# LB_BIT_i33_envelope-v03_3_3.net
KiCad netlist of a schematic drawn in EAGLE
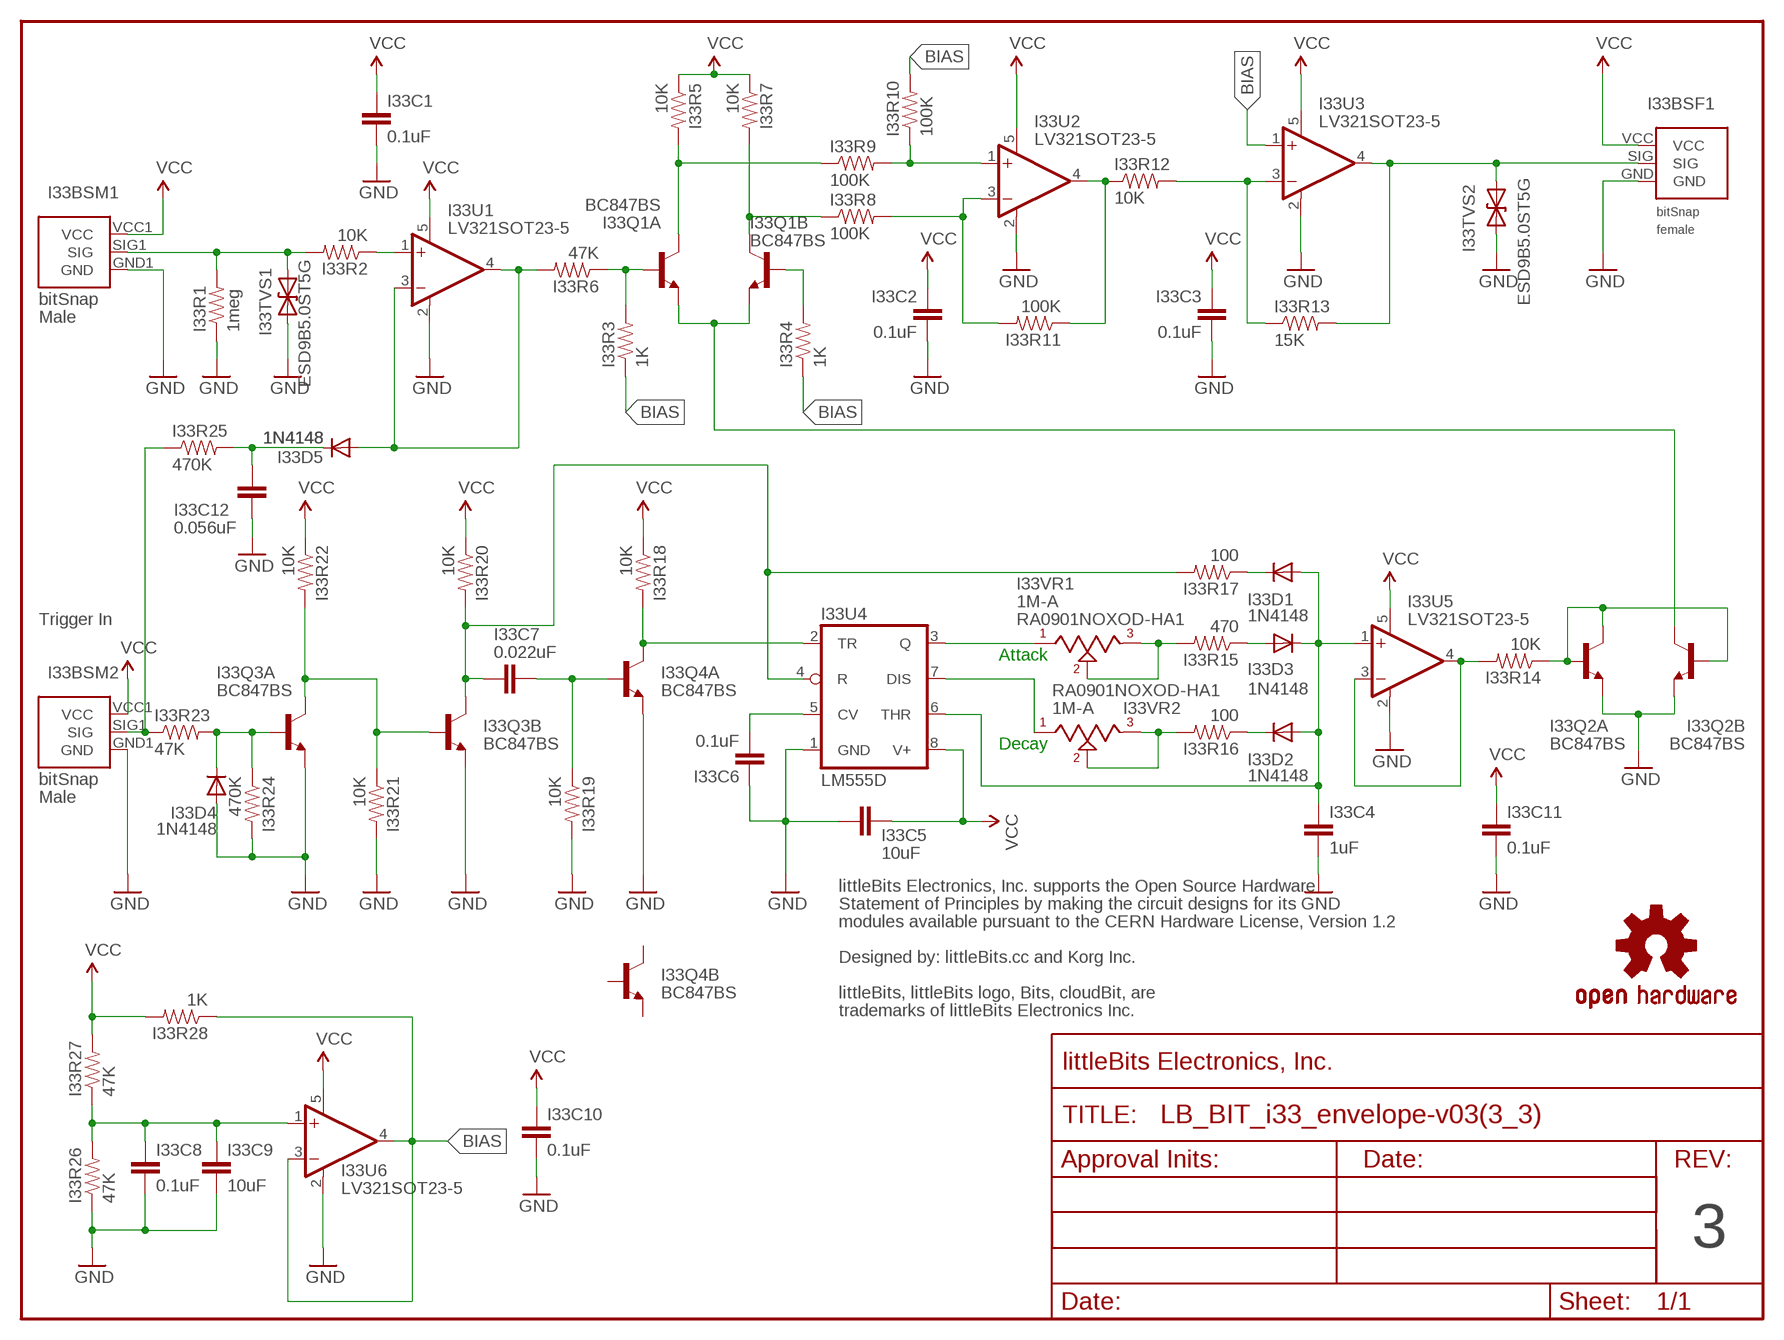
[diagram p0: schematic, sheet 1]

(export (version "E")
  (design (tool "Eeschema 10.0.6"))
  (components
    (comp (ref "I33BSF1")
      (value "BITSNAP_V03_FEMALE")
      (footprint "eagle-import:BITSNAP_V03_FEMALE")
      (libsource (lib "eagle-import") (part "BITSNAP_V03_FEMALE"))
    )
    (comp (ref "I33BSM1")
      (value "BITSNAP_V03_MALE")
      (footprint "eagle-import:BITSNAP_V03_MALE")
      (libsource (lib "eagle-import") (part "BITSNAP_V03_MALE"))
    )
    (comp (ref "I33BSM2")
      (value "BITSNAP_V03_MALE")
      (footprint "eagle-import:BITSNAP_V03_MALE")
      (libsource (lib "eagle-import") (part "BITSNAP_V03_MALE"))
    )
    (comp (ref "I33C1")
      (value "0.1uF")
      (footprint "eagle-import:CAP-0603")
      (libsource (lib "eagle-import") (part "CAPCAP-0603"))
    )
    (comp (ref "I33C2")
      (value "0.1uF")
      (footprint "eagle-import:CAP-0603")
      (libsource (lib "eagle-import") (part "CAPCAP-0603"))
    )
    (comp (ref "I33C3")
      (value "0.1uF")
      (footprint "eagle-import:CAP-0603")
      (libsource (lib "eagle-import") (part "CAPCAP-0603"))
    )
    (comp (ref "I33C4")
      (value "1uF")
      (footprint "eagle-import:CAP-0603")
      (libsource (lib "eagle-import") (part "CAPCAP-0603"))
    )
    (comp (ref "I33C5")
      (value "10uF")
      (footprint "eagle-import:CAP-0603")
      (libsource (lib "eagle-import") (part "CAPCAP-0603"))
    )
    (comp (ref "I33C6")
      (value "0.1uF")
      (footprint "eagle-import:CAP-0603")
      (libsource (lib "eagle-import") (part "CAPCAP-0603"))
    )
    (comp (ref "I33C7")
      (value "0.022uF")
      (footprint "eagle-import:CAP-0603")
      (libsource (lib "eagle-import") (part "CAPCAP-0603"))
    )
    (comp (ref "I33C8")
      (value "0.1uF")
      (footprint "eagle-import:CAP-0603")
      (libsource (lib "eagle-import") (part "CAPCAP-0603"))
    )
    (comp (ref "I33C9")
      (value "10uF")
      (footprint "eagle-import:CAP-0603")
      (libsource (lib "eagle-import") (part "CAPCAP-0603"))
    )
    (comp (ref "I33C10")
      (value "0.1uF")
      (footprint "eagle-import:CAP-0603")
      (libsource (lib "eagle-import") (part "CAPCAP-0603"))
    )
    (comp (ref "I33C11")
      (value "0.1uF")
      (footprint "eagle-import:CAP-0603")
      (libsource (lib "eagle-import") (part "CAPCAP-0603"))
    )
    (comp (ref "I33C12")
      (value "0.056uF")
      (footprint "eagle-import:CAP-0603")
      (libsource (lib "eagle-import") (part "CAPCAP-0603"))
    )
    (comp (ref "I33D1")
      (value "1N4148")
      (footprint "eagle-import:SOD-323")
      (libsource (lib "eagle-import") (part "DIODESOD"))
    )
    (comp (ref "I33D2")
      (value "1N4148")
      (footprint "eagle-import:SOD-323")
      (libsource (lib "eagle-import") (part "DIODESOD"))
    )
    (comp (ref "I33D3")
      (value "1N4148")
      (footprint "eagle-import:SOD-323")
      (libsource (lib "eagle-import") (part "DIODESOD"))
    )
    (comp (ref "I33D4")
      (value "1N4148")
      (footprint "eagle-import:SOD-323")
      (libsource (lib "eagle-import") (part "DIODESOD"))
    )
    (comp (ref "I33D5")
      (value "1N4148")
      (footprint "eagle-import:SOD-323")
      (libsource (lib "eagle-import") (part "DIODESOD"))
    )
    (comp (ref "I33Q1")
      (value "BC847BS")
      (footprint "eagle-import:SOT-363_PHILLIPS")
      (libsource (lib "eagle-import") (part "TRANS-BJT_NPN-DUAL-BC847BS"))
    )
    (comp (ref "I33Q2")
      (value "BC847BS")
      (footprint "eagle-import:SOT-363_PHILLIPS")
      (libsource (lib "eagle-import") (part "TRANS-BJT_NPN-DUAL-BC847BS"))
    )
    (comp (ref "I33Q3")
      (value "BC847BS")
      (footprint "eagle-import:SOT-363_PHILLIPS")
      (libsource (lib "eagle-import") (part "TRANS-BJT_NPN-DUAL-BC847BS"))
    )
    (comp (ref "I33Q4")
      (value "BC847BS")
      (footprint "eagle-import:SOT-363_PHILLIPS")
      (libsource (lib "eagle-import") (part "TRANS-BJT_NPN-DUAL-BC847BS"))
    )
    (comp (ref "I33R1")
      (value "1meg")
      (footprint "eagle-import:RES-0603")
      (libsource (lib "eagle-import") (part "RESISTOR0603"))
    )
    (comp (ref "I33R2")
      (value "10K")
      (footprint "eagle-import:RES-0603")
      (libsource (lib "eagle-import") (part "RESISTOR0603"))
    )
    (comp (ref "I33R3")
      (value "1K")
      (footprint "eagle-import:RES-0603")
      (libsource (lib "eagle-import") (part "RESISTOR0603"))
    )
    (comp (ref "I33R4")
      (value "1K")
      (footprint "eagle-import:RES-0603")
      (libsource (lib "eagle-import") (part "RESISTOR0603"))
    )
    (comp (ref "I33R5")
      (value "10K")
      (footprint "eagle-import:RES-0603")
      (libsource (lib "eagle-import") (part "RESISTOR0603"))
    )
    (comp (ref "I33R6")
      (value "47K")
      (footprint "eagle-import:RES-0603")
      (libsource (lib "eagle-import") (part "RESISTOR0603"))
    )
    (comp (ref "I33R7")
      (value "10K")
      (footprint "eagle-import:RES-0603")
      (libsource (lib "eagle-import") (part "RESISTOR0603"))
    )
    (comp (ref "I33R8")
      (value "100K")
      (footprint "eagle-import:RES-0603")
      (libsource (lib "eagle-import") (part "RESISTOR0603"))
    )
    (comp (ref "I33R9")
      (value "100K")
      (footprint "eagle-import:RES-0603")
      (libsource (lib "eagle-import") (part "RESISTOR0603"))
    )
    (comp (ref "I33R10")
      (value "100K")
      (footprint "eagle-import:RES-0603")
      (libsource (lib "eagle-import") (part "RESISTOR0603"))
    )
    (comp (ref "I33R11")
      (value "100K")
      (footprint "eagle-import:RES-0603")
      (libsource (lib "eagle-import") (part "RESISTOR0603"))
    )
    (comp (ref "I33R12")
      (value "10K")
      (footprint "eagle-import:RES-0603")
      (libsource (lib "eagle-import") (part "RESISTOR0603"))
    )
    (comp (ref "I33R13")
      (value "15K")
      (footprint "eagle-import:RES-0603")
      (libsource (lib "eagle-import") (part "RESISTOR0603"))
    )
    (comp (ref "I33R14")
      (value "10K")
      (footprint "eagle-import:RES-0603")
      (libsource (lib "eagle-import") (part "RESISTOR0603"))
    )
    (comp (ref "I33R15")
      (value "470")
      (footprint "eagle-import:RES-0603")
      (libsource (lib "eagle-import") (part "RESISTOR0603"))
    )
    (comp (ref "I33R16")
      (value "100")
      (footprint "eagle-import:RES-0603")
      (libsource (lib "eagle-import") (part "RESISTOR0603"))
    )
    (comp (ref "I33R17")
      (value "100")
      (footprint "eagle-import:RES-0603")
      (libsource (lib "eagle-import") (part "RESISTOR0603"))
    )
    (comp (ref "I33R18")
      (value "10K")
      (footprint "eagle-import:RES-0603")
      (libsource (lib "eagle-import") (part "RESISTOR0603"))
    )
    (comp (ref "I33R19")
      (value "10K")
      (footprint "eagle-import:RES-0603")
      (libsource (lib "eagle-import") (part "RESISTOR0603"))
    )
    (comp (ref "I33R20")
      (value "10K")
      (footprint "eagle-import:RES-0603")
      (libsource (lib "eagle-import") (part "RESISTOR0603"))
    )
    (comp (ref "I33R21")
      (value "10K")
      (footprint "eagle-import:RES-0603")
      (libsource (lib "eagle-import") (part "RESISTOR0603"))
    )
    (comp (ref "I33R22")
      (value "10K")
      (footprint "eagle-import:RES-0603")
      (libsource (lib "eagle-import") (part "RESISTOR0603"))
    )
    (comp (ref "I33R23")
      (value "47K")
      (footprint "eagle-import:RES-0603")
      (libsource (lib "eagle-import") (part "RESISTOR0603"))
    )
    (comp (ref "I33R24")
      (value "470K")
      (footprint "eagle-import:RES-0603")
      (libsource (lib "eagle-import") (part "RESISTOR0603"))
    )
    (comp (ref "I33R25")
      (value "470K")
      (footprint "eagle-import:RES-0603")
      (libsource (lib "eagle-import") (part "RESISTOR0603"))
    )
    (comp (ref "I33R26")
      (value "47K")
      (footprint "eagle-import:RES-0603")
      (libsource (lib "eagle-import") (part "RESISTOR0603"))
    )
    (comp (ref "I33R27")
      (value "47K")
      (footprint "eagle-import:RES-0603")
      (libsource (lib "eagle-import") (part "RESISTOR0603"))
    )
    (comp (ref "I33R28")
      (value "1K")
      (footprint "eagle-import:RES-0603")
      (libsource (lib "eagle-import") (part "RESISTOR0603"))
    )
    (comp (ref "I33TVS1")
      (value "ESD9B5.0ST5G")
      (footprint "eagle-import:SOD-923")
      (libsource (lib "eagle-import") (part "DIODE-TVSSOD-923"))
    )
    (comp (ref "I33TVS2")
      (value "ESD9B5.0ST5G")
      (footprint "eagle-import:SOD-923")
      (libsource (lib "eagle-import") (part "DIODE-TVSSOD-923"))
    )
    (comp (ref "I33U1")
      (value "LV321SOT23-5")
      (footprint "eagle-import:SOT23-5")
      (libsource (lib "eagle-import") (part "LV321SOT23-5"))
    )
    (comp (ref "I33U2")
      (value "LV321SOT23-5")
      (footprint "eagle-import:SOT23-5")
      (libsource (lib "eagle-import") (part "LV321SOT23-5"))
    )
    (comp (ref "I33U3")
      (value "LV321SOT23-5")
      (footprint "eagle-import:SOT23-5")
      (libsource (lib "eagle-import") (part "LV321SOT23-5"))
    )
    (comp (ref "I33U4")
      (value "LM555D")
      (footprint "eagle-import:SO08")
      (libsource (lib "eagle-import") (part "LM555D"))
    )
    (comp (ref "I33U5")
      (value "LV321SOT23-5")
      (footprint "eagle-import:SOT23-5")
      (libsource (lib "eagle-import") (part "LV321SOT23-5"))
    )
    (comp (ref "I33U6")
      (value "LV321SOT23-5")
      (footprint "eagle-import:SOT23-5")
      (libsource (lib "eagle-import") (part "LV321SOT23-5"))
    )
    (comp (ref "I33VR1")
      (value "1M-A")
      (footprint "eagle-import:ALPS_POT")
      (libsource (lib "eagle-import") (part "ALPS_POTTH"))
    )
    (comp (ref "I33VR2")
      (value "1M-A")
      (footprint "eagle-import:ALPS_POT")
      (libsource (lib "eagle-import") (part "ALPS_POTTH"))
    )
    (comp (ref "U$1")
      (value "FRAME-LETTER-OHWOHW")
      (footprint "eagle-import:FABDWG01-OHW")
      (libsource (lib "eagle-import") (part "FRAME-LETTER-OHWOHW"))
    )
    (comp (ref "U$3")
      (value "OSHWCREDIT-KORG")
      (footprint "eagle-import:OSHWCREDIT-KORG")
      (libsource (lib "eagle-import") (part "OSHWCREDIT-KORG"))
    )
    (comp (ref "U$9")
      (value "OSHW-LOGOL")
      (footprint "eagle-import:OSHW-LOGO-L")
      (libsource (lib "eagle-import") (part "OSHW-LOGOL"))
    )
  )
  (nets
    (net (code "1") (name "BIAS") (class "Default")
      (node (ref "I33R10") (pin "2") (pinfunction "2_2") (pintype "passive"))
      (node (ref "I33R28") (pin "1") (pinfunction "1_1") (pintype "passive"))
      (node (ref "I33R3") (pin "1") (pinfunction "1_1") (pintype "passive"))
      (node (ref "I33R4") (pin "1") (pinfunction "1_1") (pintype "passive"))
      (node (ref "I33U3") (pin "1") (pinfunction "+IN_1") (pintype "input"))
      (node (ref "I33U6") (pin "3") (pinfunction "-IN_3") (pintype "input"))
      (node (ref "I33U6") (pin "4") (pinfunction "OUT_4") (pintype "output"))
    )
    (net (code "2") (name "GND") (class "Default")
      (node (ref "I33BSF1") (pin "GND") (pinfunction "GND_GND") (pintype "bidirectional"))
      (node (ref "I33BSM1") (pin "GND1") (pinfunction "GND_GND1") (pintype "bidirectional"))
      (node (ref "I33BSM2") (pin "GND1") (pinfunction "GND_GND1") (pintype "bidirectional"))
      (node (ref "I33C1") (pin "2") (pinfunction "2_2") (pintype "passive"))
      (node (ref "I33C10") (pin "2") (pinfunction "2_2") (pintype "passive"))
      (node (ref "I33C11") (pin "2") (pinfunction "2_2") (pintype "passive"))
      (node (ref "I33C12") (pin "2") (pinfunction "2_2") (pintype "passive"))
      (node (ref "I33C2") (pin "2") (pinfunction "2_2") (pintype "passive"))
      (node (ref "I33C3") (pin "2") (pinfunction "2_2") (pintype "passive"))
      (node (ref "I33C4") (pin "2") (pinfunction "2_2") (pintype "passive"))
      (node (ref "I33C5") (pin "1") (pinfunction "1_1") (pintype "passive"))
      (node (ref "I33C6") (pin "1") (pinfunction "1_1") (pintype "passive"))
      (node (ref "I33C8") (pin "2") (pinfunction "2_2") (pintype "passive"))
      (node (ref "I33C9") (pin "2") (pinfunction "2_2") (pintype "passive"))
      (node (ref "I33D4") (pin "2") (pinfunction "A_2") (pintype "passive"))
      (node (ref "I33Q2") (pin "1") (pinfunction "E_1") (pintype "passive"))
      (node (ref "I33Q2") (pin "4") (pinfunction "E_4") (pintype "passive"))
      (node (ref "I33Q3") (pin "1") (pinfunction "E_1") (pintype "passive"))
      (node (ref "I33Q3") (pin "4") (pinfunction "E_4") (pintype "passive"))
      (node (ref "I33Q4") (pin "1") (pinfunction "E_1") (pintype "passive"))
      (node (ref "I33R1") (pin "1") (pinfunction "1_1") (pintype "passive"))
      (node (ref "I33R19") (pin "2") (pinfunction "2_2") (pintype "passive"))
      (node (ref "I33R21") (pin "2") (pinfunction "2_2") (pintype "passive"))
      (node (ref "I33R24") (pin "2") (pinfunction "2_2") (pintype "passive"))
      (node (ref "I33R26") (pin "1") (pinfunction "1_1") (pintype "passive"))
      (node (ref "I33TVS1") (pin "1") (pinfunction "A_1") (pintype "passive"))
      (node (ref "I33TVS2") (pin "1") (pinfunction "A_1") (pintype "passive"))
      (node (ref "I33U1") (pin "2") (pinfunction "V-_2") (pintype "power_in"))
      (node (ref "I33U2") (pin "2") (pinfunction "V-_2") (pintype "power_in"))
      (node (ref "I33U3") (pin "2") (pinfunction "V-_2") (pintype "power_in"))
      (node (ref "I33U4") (pin "1") (pinfunction "GND_1") (pintype "power_in"))
      (node (ref "I33U5") (pin "2") (pinfunction "V-_2") (pintype "power_in"))
      (node (ref "I33U6") (pin "2") (pinfunction "V-_2") (pintype "power_in"))
    )
    (net (code "3") (name "Net-(I33BSM1-SIG)") (class "Default")
      (node (ref "I33BSM1") (pin "SIG1") (pinfunction "SIG_SIG1") (pintype "bidirectional"))
      (node (ref "I33R1") (pin "2") (pinfunction "2_2") (pintype "passive"))
      (node (ref "I33R2") (pin "2") (pinfunction "2_2") (pintype "passive"))
      (node (ref "I33TVS1") (pin "2") (pinfunction "C_2") (pintype "passive"))
    )
    (net (code "4") (name "Net-(I33BSM2-SIG)") (class "Default")
      (node (ref "I33BSM2") (pin "SIG1") (pinfunction "SIG_SIG1") (pintype "bidirectional"))
      (node (ref "I33R23") (pin "1") (pinfunction "1_1") (pintype "passive"))
      (node (ref "I33R25") (pin "1") (pinfunction "1_1") (pintype "passive"))
    )
    (net (code "5") (name "Net-(I33D1-A)") (class "Default")
      (node (ref "I33C4") (pin "1") (pinfunction "1_1") (pintype "passive"))
      (node (ref "I33D1") (pin "2") (pinfunction "A_2") (pintype "passive"))
      (node (ref "I33D2") (pin "2") (pinfunction "A_2") (pintype "passive"))
      (node (ref "I33D3") (pin "1") (pinfunction "C_1") (pintype "passive"))
      (node (ref "I33U4") (pin "6") (pinfunction "THR_6") (pintype "input"))
      (node (ref "I33U5") (pin "1") (pinfunction "+IN_1") (pintype "input"))
    )
    (net (code "6") (name "Net-(I33D1-C)") (class "Default")
      (node (ref "I33D1") (pin "1") (pinfunction "C_1") (pintype "passive"))
      (node (ref "I33R17") (pin "1") (pinfunction "1_1") (pintype "passive"))
    )
    (net (code "7") (name "Net-(I33D2-C)") (class "Default")
      (node (ref "I33D2") (pin "1") (pinfunction "C_1") (pintype "passive"))
      (node (ref "I33R16") (pin "1") (pinfunction "1_1") (pintype "passive"))
    )
    (net (code "8") (name "Net-(I33D3-A)") (class "Default")
      (node (ref "I33D3") (pin "2") (pinfunction "A_2") (pintype "passive"))
      (node (ref "I33R15") (pin "1") (pinfunction "1_1") (pintype "passive"))
    )
    (net (code "9") (name "Net-(I33D4-C)") (class "Default")
      (node (ref "I33D4") (pin "1") (pinfunction "C_1") (pintype "passive"))
      (node (ref "I33Q3") (pin "2") (pinfunction "B_2") (pintype "passive"))
      (node (ref "I33R23") (pin "2") (pinfunction "2_2") (pintype "passive"))
      (node (ref "I33R24") (pin "1") (pinfunction "1_1") (pintype "passive"))
    )
    (net (code "10") (name "Net-(I33D5-A)") (class "Default")
      (node (ref "I33D5") (pin "2") (pinfunction "A_2") (pintype "passive"))
      (node (ref "I33R6") (pin "2") (pinfunction "2_2") (pintype "passive"))
      (node (ref "I33U1") (pin "3") (pinfunction "-IN_3") (pintype "input"))
      (node (ref "I33U1") (pin "4") (pinfunction "OUT_4") (pintype "output"))
    )
    (net (code "11") (name "Net-(I33D5-C)") (class "Default")
      (node (ref "I33C12") (pin "1") (pinfunction "1_1") (pintype "passive"))
      (node (ref "I33D5") (pin "1") (pinfunction "C_1") (pintype "passive"))
      (node (ref "I33R25") (pin "2") (pinfunction "2_2") (pintype "passive"))
    )
    (net (code "12") (name "Net-(I33Q1A-B)") (class "Default")
      (node (ref "I33Q1") (pin "2") (pinfunction "B_2") (pintype "passive"))
      (node (ref "I33R3") (pin "2") (pinfunction "2_2") (pintype "passive"))
      (node (ref "I33R6") (pin "1") (pinfunction "1_1") (pintype "passive"))
    )
    (net (code "13") (name "Net-(I33Q1A-C)") (class "Default")
      (node (ref "I33Q1") (pin "6") (pinfunction "C_6") (pintype "passive"))
      (node (ref "I33R5") (pin "2") (pinfunction "2_2") (pintype "passive"))
      (node (ref "I33R9") (pin "1") (pinfunction "1_1") (pintype "passive"))
    )
    (net (code "14") (name "Net-(I33Q1A-E)") (class "Default")
      (node (ref "I33Q1") (pin "1") (pinfunction "E_1") (pintype "passive"))
      (node (ref "I33Q1") (pin "4") (pinfunction "E_4") (pintype "passive"))
      (node (ref "I33Q2") (pin "3") (pinfunction "C_3") (pintype "passive"))
    )
    (net (code "15") (name "Net-(I33Q1B-B)") (class "Default")
      (node (ref "I33Q1") (pin "5") (pinfunction "B_5") (pintype "passive"))
      (node (ref "I33R4") (pin "2") (pinfunction "2_2") (pintype "passive"))
    )
    (net (code "16") (name "Net-(I33Q1B-C)") (class "Default")
      (node (ref "I33Q1") (pin "3") (pinfunction "C_3") (pintype "passive"))
      (node (ref "I33R7") (pin "2") (pinfunction "2_2") (pintype "passive"))
      (node (ref "I33R8") (pin "1") (pinfunction "1_1") (pintype "passive"))
    )
    (net (code "17") (name "Net-(I33Q2A-B)") (class "Default")
      (node (ref "I33Q2") (pin "2") (pinfunction "B_2") (pintype "passive"))
      (node (ref "I33Q2") (pin "5") (pinfunction "B_5") (pintype "passive"))
      (node (ref "I33Q2") (pin "6") (pinfunction "C_6") (pintype "passive"))
      (node (ref "I33R14") (pin "1") (pinfunction "1_1") (pintype "passive"))
    )
    (net (code "18") (name "Net-(I33Q3A-C)") (class "Default")
      (node (ref "I33Q3") (pin "5") (pinfunction "B_5") (pintype "passive"))
      (node (ref "I33Q3") (pin "6") (pinfunction "C_6") (pintype "passive"))
      (node (ref "I33R21") (pin "1") (pinfunction "1_1") (pintype "passive"))
      (node (ref "I33R22") (pin "2") (pinfunction "2_2") (pintype "passive"))
    )
    (net (code "19") (name "Net-(I33Q3B-C)") (class "Default")
      (node (ref "I33C7") (pin "2") (pinfunction "2_2") (pintype "passive"))
      (node (ref "I33Q3") (pin "3") (pinfunction "C_3") (pintype "passive"))
      (node (ref "I33R17") (pin "2") (pinfunction "2_2") (pintype "passive"))
      (node (ref "I33R20") (pin "2") (pinfunction "2_2") (pintype "passive"))
      (node (ref "I33U4") (pin "4") (pinfunction "R_4") (pintype "input"))
    )
    (net (code "20") (name "Net-(I33Q4A-B)") (class "Default")
      (node (ref "I33C7") (pin "1") (pinfunction "1_1") (pintype "passive"))
      (node (ref "I33Q4") (pin "2") (pinfunction "B_2") (pintype "passive"))
      (node (ref "I33R19") (pin "1") (pinfunction "1_1") (pintype "passive"))
    )
    (net (code "21") (name "Net-(I33Q4A-C)") (class "Default")
      (node (ref "I33Q4") (pin "6") (pinfunction "C_6") (pintype "passive"))
      (node (ref "I33R18") (pin "2") (pinfunction "2_2") (pintype "passive"))
      (node (ref "I33U4") (pin "2") (pinfunction "TR_2") (pintype "input"))
    )
    (net (code "22") (name "Net-(I33R15-Pad2)") (class "Default")
      (node (ref "I33R15") (pin "2") (pinfunction "2_2") (pintype "passive"))
      (node (ref "I33VR1") (pin "2") (pinfunction "2_2") (pintype "passive"))
      (node (ref "I33VR1") (pin "3") (pinfunction "3_3") (pintype "passive"))
    )
    (net (code "23") (name "Net-(I33R16-Pad2)") (class "Default")
      (node (ref "I33R16") (pin "2") (pinfunction "2_2") (pintype "passive"))
      (node (ref "I33VR2") (pin "2") (pinfunction "2_2") (pintype "passive"))
      (node (ref "I33VR2") (pin "3") (pinfunction "3_3") (pintype "passive"))
    )
    (net (code "24") (name "Net-(I33TVS2-C)") (class "Default")
      (node (ref "I33BSF1") (pin "SIG") (pinfunction "SIG_SIG") (pintype "bidirectional"))
      (node (ref "I33R13") (pin "2") (pinfunction "2_2") (pintype "passive"))
      (node (ref "I33TVS2") (pin "2") (pinfunction "C_2") (pintype "passive"))
      (node (ref "I33U3") (pin "4") (pinfunction "OUT_4") (pintype "output"))
    )
    (net (code "25") (name "Net-(I33U1-+IN)") (class "Default")
      (node (ref "I33R2") (pin "1") (pinfunction "1_1") (pintype "passive"))
      (node (ref "I33U1") (pin "1") (pinfunction "+IN_1") (pintype "input"))
    )
    (net (code "26") (name "Net-(I33U2-+IN)") (class "Default")
      (node (ref "I33R10") (pin "1") (pinfunction "1_1") (pintype "passive"))
      (node (ref "I33R9") (pin "2") (pinfunction "2_2") (pintype "passive"))
      (node (ref "I33U2") (pin "1") (pinfunction "+IN_1") (pintype "input"))
    )
    (net (code "27") (name "Net-(I33U2--IN)") (class "Default")
      (node (ref "I33R11") (pin "2") (pinfunction "2_2") (pintype "passive"))
      (node (ref "I33R8") (pin "2") (pinfunction "2_2") (pintype "passive"))
      (node (ref "I33U2") (pin "3") (pinfunction "-IN_3") (pintype "input"))
    )
    (net (code "28") (name "Net-(I33U2-OUT)") (class "Default")
      (node (ref "I33R11") (pin "1") (pinfunction "1_1") (pintype "passive"))
      (node (ref "I33R12") (pin "1") (pinfunction "1_1") (pintype "passive"))
      (node (ref "I33U2") (pin "4") (pinfunction "OUT_4") (pintype "output"))
    )
    (net (code "29") (name "Net-(I33U3--IN)") (class "Default")
      (node (ref "I33R12") (pin "2") (pinfunction "2_2") (pintype "passive"))
      (node (ref "I33R13") (pin "1") (pinfunction "1_1") (pintype "passive"))
      (node (ref "I33U3") (pin "3") (pinfunction "-IN_3") (pintype "input"))
    )
    (net (code "30") (name "Net-(I33U4-CV)") (class "Default")
      (node (ref "I33C6") (pin "2") (pinfunction "2_2") (pintype "passive"))
      (node (ref "I33U4") (pin "5") (pinfunction "CV_5") (pintype "input"))
    )
    (net (code "31") (name "Net-(I33U4-DIS)") (class "Default")
      (node (ref "I33U4") (pin "7") (pinfunction "DIS_7") (pintype "input"))
      (node (ref "I33VR2") (pin "1") (pinfunction "1_1") (pintype "passive"))
    )
    (net (code "32") (name "Net-(I33U4-Q)") (class "Default")
      (node (ref "I33U4") (pin "3") (pinfunction "Q_3") (pintype "output"))
      (node (ref "I33VR1") (pin "1") (pinfunction "1_1") (pintype "passive"))
    )
    (net (code "33") (name "Net-(I33U5--IN)") (class "Default")
      (node (ref "I33R14") (pin "2") (pinfunction "2_2") (pintype "passive"))
      (node (ref "I33U5") (pin "3") (pinfunction "-IN_3") (pintype "input"))
      (node (ref "I33U5") (pin "4") (pinfunction "OUT_4") (pintype "output"))
    )
    (net (code "34") (name "Net-(I33U6-+IN)") (class "Default")
      (node (ref "I33C8") (pin "1") (pinfunction "1_1") (pintype "passive"))
      (node (ref "I33C9") (pin "1") (pinfunction "1_1") (pintype "passive"))
      (node (ref "I33R26") (pin "2") (pinfunction "2_2") (pintype "passive"))
      (node (ref "I33R27") (pin "1") (pinfunction "1_1") (pintype "passive"))
      (node (ref "I33U6") (pin "1") (pinfunction "+IN_1") (pintype "input"))
    )
    (net (code "35") (name "VCC") (class "Default")
      (node (ref "I33BSF1") (pin "VCC") (pinfunction "VCC_VCC") (pintype "bidirectional"))
      (node (ref "I33BSM1") (pin "VCC1") (pinfunction "VCC_VCC1") (pintype "bidirectional"))
      (node (ref "I33BSM2") (pin "VCC1") (pinfunction "VCC_VCC1") (pintype "bidirectional"))
      (node (ref "I33C1") (pin "1") (pinfunction "1_1") (pintype "passive"))
      (node (ref "I33C10") (pin "1") (pinfunction "1_1") (pintype "passive"))
      (node (ref "I33C11") (pin "1") (pinfunction "1_1") (pintype "passive"))
      (node (ref "I33C2") (pin "1") (pinfunction "1_1") (pintype "passive"))
      (node (ref "I33C3") (pin "1") (pinfunction "1_1") (pintype "passive"))
      (node (ref "I33C5") (pin "2") (pinfunction "2_2") (pintype "passive"))
      (node (ref "I33R18") (pin "1") (pinfunction "1_1") (pintype "passive"))
      (node (ref "I33R20") (pin "1") (pinfunction "1_1") (pintype "passive"))
      (node (ref "I33R22") (pin "1") (pinfunction "1_1") (pintype "passive"))
      (node (ref "I33R27") (pin "2") (pinfunction "2_2") (pintype "passive"))
      (node (ref "I33R28") (pin "2") (pinfunction "2_2") (pintype "passive"))
      (node (ref "I33R5") (pin "1") (pinfunction "1_1") (pintype "passive"))
      (node (ref "I33R7") (pin "1") (pinfunction "1_1") (pintype "passive"))
      (node (ref "I33U1") (pin "5") (pinfunction "V+_5") (pintype "power_in"))
      (node (ref "I33U2") (pin "5") (pinfunction "V+_5") (pintype "power_in"))
      (node (ref "I33U3") (pin "5") (pinfunction "V+_5") (pintype "power_in"))
      (node (ref "I33U4") (pin "8") (pinfunction "V+_8") (pintype "power_in"))
      (node (ref "I33U5") (pin "5") (pinfunction "V+_5") (pintype "power_in"))
      (node (ref "I33U6") (pin "5") (pinfunction "V+_5") (pintype "power_in"))
    )
    (net (code "36") (name "unconnected-(I33Q4B-B-Pad5)") (class "Default")
      (node (ref "I33Q4") (pin "5") (pinfunction "B_5") (pintype "passive"))
    )
    (net (code "37") (name "unconnected-(I33Q4B-C-Pad3)") (class "Default")
      (node (ref "I33Q4") (pin "3") (pinfunction "C_3") (pintype "passive"))
    )
    (net (code "38") (name "unconnected-(I33Q4B-E-Pad4)") (class "Default")
      (node (ref "I33Q4") (pin "4") (pinfunction "E_4") (pintype "passive"))
    )
  )
)
